# Adafruit_MicroUSB_Lipo.net
KiCad netlist of a schematic drawn in EAGLE
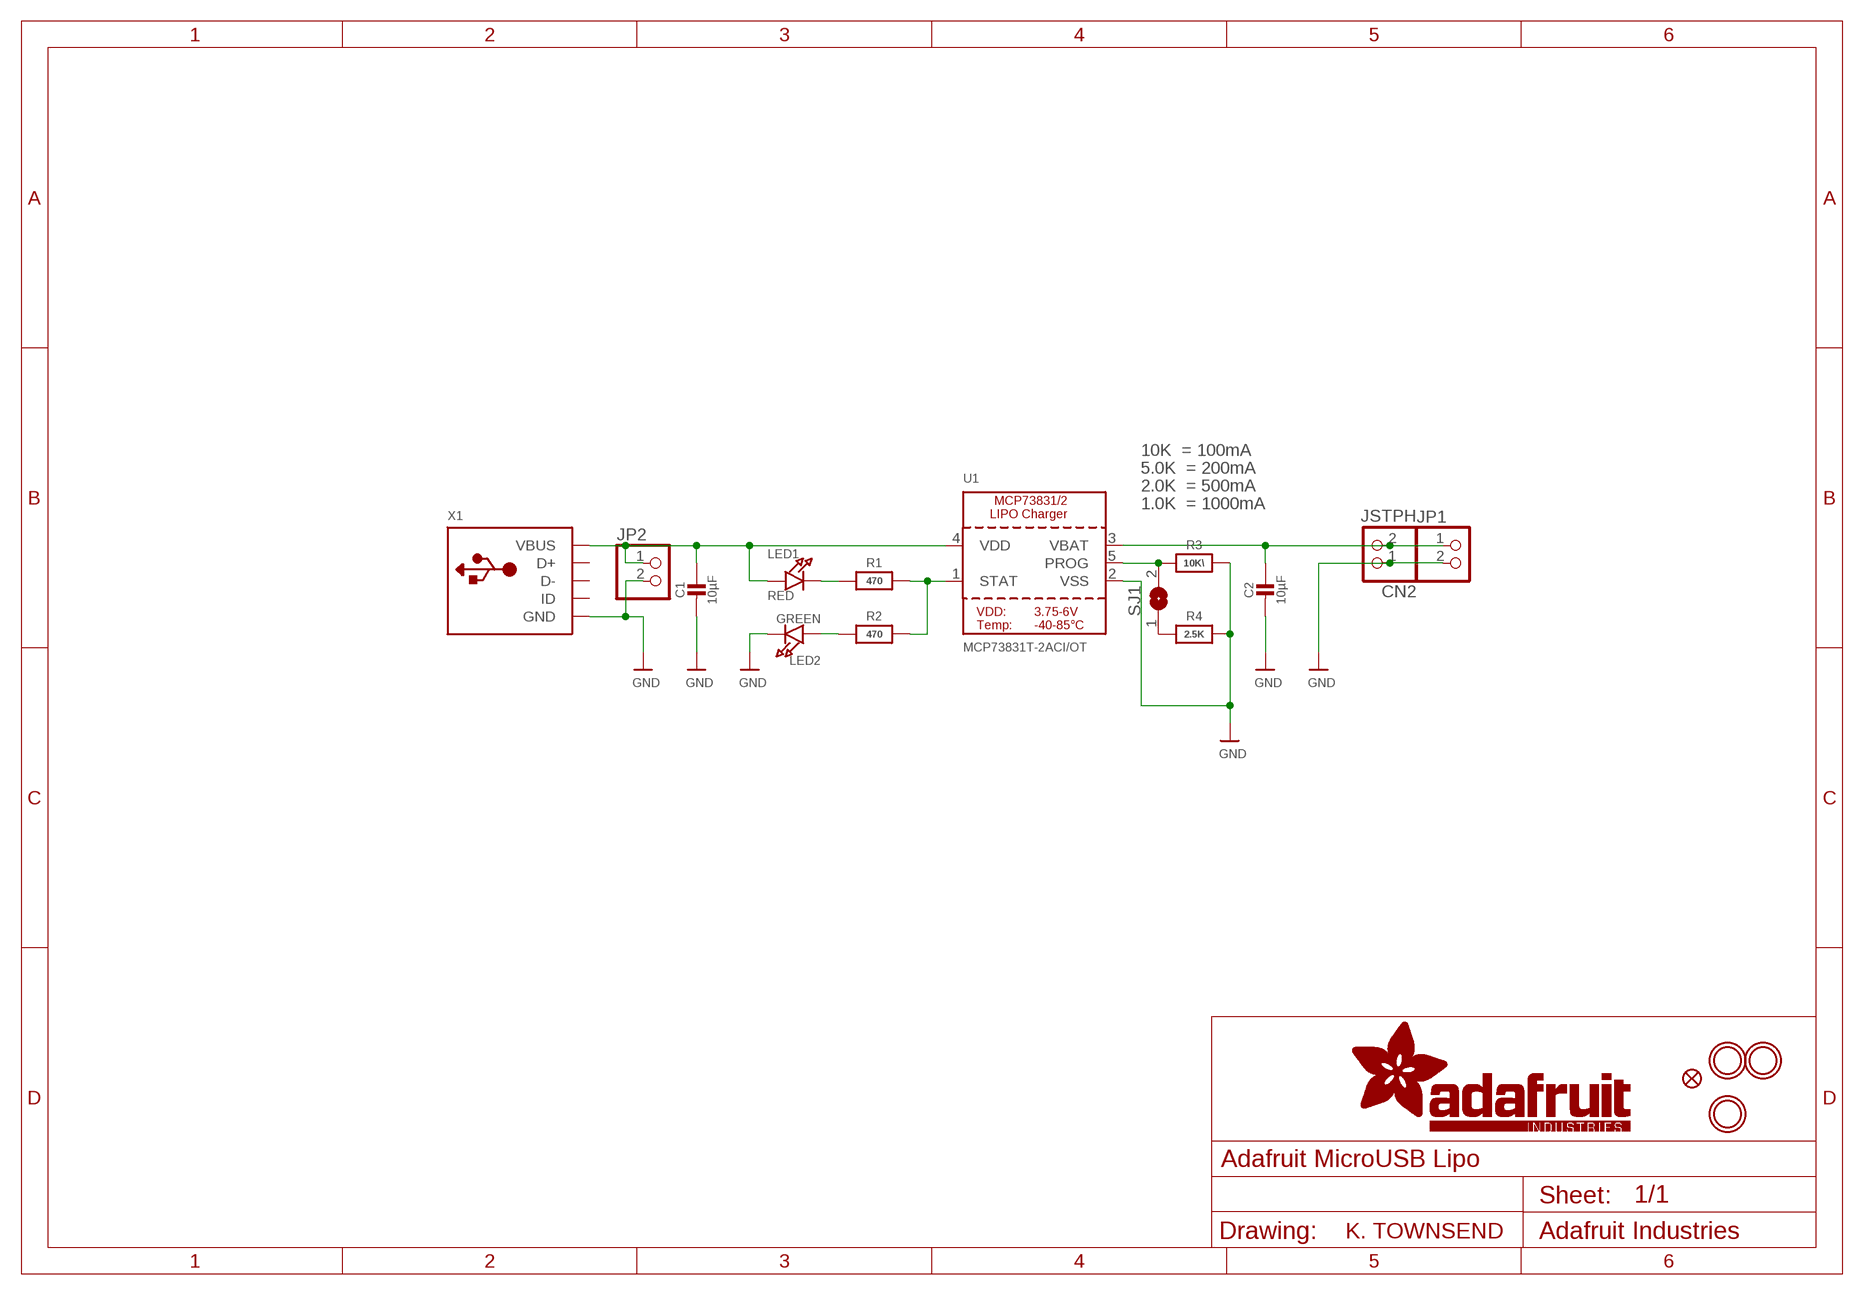
[diagram p0: schematic, sheet 1]

(export (version "E")
  (design (tool "Eeschema 10.0.6"))
  (components
    (comp (ref "C1")
      (value "10µF")
      (footprint "eagle-import:0805-NO")
      (libsource (lib "eagle-import") (part "CAP_CERAMIC0805-NOOUTLINE"))
    )
    (comp (ref "C2")
      (value "10µF")
      (footprint "eagle-import:0805-NO")
      (libsource (lib "eagle-import") (part "CAP_CERAMIC0805-NOOUTLINE"))
    )
    (comp (ref "CN2")
      (value "JSTPH")
      (footprint "eagle-import:JSTPH2")
      (libsource (lib "eagle-import") (part "JST_2PIN"))
    )
    (comp (ref "FID1")
      (value "FIDUCIAL\"\"")
      (footprint "eagle-import:FIDUCIAL_1MM")
      (libsource (lib "eagle-import") (part "FIDUCIAL{dblquote}{dblquote}"))
    )
    (comp (ref "JP1")
      (value "HEADER-1X2ROUND")
      (footprint "eagle-import:1X02_ROUND")
      (libsource (lib "eagle-import") (part "HEADER-1X2ROUND"))
    )
    (comp (ref "JP2")
      (value "HEADER-1X2ROUND")
      (footprint "eagle-import:1X02_ROUND")
      (libsource (lib "eagle-import") (part "HEADER-1X2ROUND"))
    )
    (comp (ref "LED1")
      (value "RED")
      (footprint "eagle-import:CHIPLED_0805_NOOUTLINE")
      (libsource (lib "eagle-import") (part "LED0805_NOOUTLINE"))
    )
    (comp (ref "LED2")
      (value "GREEN")
      (footprint "eagle-import:CHIPLED_0805_NOOUTLINE")
      (libsource (lib "eagle-import") (part "LED0805_NOOUTLINE"))
    )
    (comp (ref "R1")
      (value "470")
      (footprint "eagle-import:0805-NO")
      (libsource (lib "eagle-import") (part "RESISTOR0805_NOOUTLINE"))
    )
    (comp (ref "R2")
      (value "470")
      (footprint "eagle-import:0805-NO")
      (libsource (lib "eagle-import") (part "RESISTOR0805_NOOUTLINE"))
    )
    (comp (ref "R3")
      (value "10K\\")
      (footprint "eagle-import:0805-NO")
      (libsource (lib "eagle-import") (part "RESISTOR0805_NOOUTLINE"))
    )
    (comp (ref "R4")
      (value "2.5K")
      (footprint "eagle-import:0805-NO")
      (libsource (lib "eagle-import") (part "RESISTOR0805_NOOUTLINE"))
    )
    (comp (ref "SJ1")
      (value "SOLDERJUMPER")
      (footprint "eagle-import:SOLDERJUMPER_ARROW_NOPASTE")
      (libsource (lib "eagle-import") (part "SOLDERJUMPER"))
    )
    (comp (ref "U$9")
      (value "MOUNTINGHOLE2.5")
      (footprint "eagle-import:MOUNTINGHOLE_2.5_PLATED")
      (libsource (lib "eagle-import") (part "MOUNTINGHOLE2.5"))
    )
    (comp (ref "U$11")
      (value "MOUNTINGHOLE2.5")
      (footprint "eagle-import:MOUNTINGHOLE_2.5_PLATED")
      (libsource (lib "eagle-import") (part "MOUNTINGHOLE2.5"))
    )
    (comp (ref "U$12")
      (value "MOUNTINGHOLE2.5")
      (footprint "eagle-import:MOUNTINGHOLE_2.5_PLATED")
      (libsource (lib "eagle-import") (part "MOUNTINGHOLE2.5"))
    )
    (comp (ref "U1")
      (value "MCP73831T-2ACI/OT")
      (footprint "eagle-import:SOT23-5")
      (libsource (lib "eagle-import") (part "MCP73831/2"))
    )
    (comp (ref "X1")
      (value "USBMICRO_20329")
      (footprint "eagle-import:4UCONN_20329")
      (libsource (lib "eagle-import") (part "USBMICRO_20329"))
    )
  )
  (nets
    (net (code "1") (name "GND") (class "Default")
      (node (ref "C1") (pin "2") (pinfunction "2_2") (pintype "passive"))
      (node (ref "C2") (pin "2") (pinfunction "2_2") (pintype "passive"))
      (node (ref "CN2") (pin "1") (pinfunction "1_1") (pintype "passive"))
      (node (ref "JP1") (pin "2") (pinfunction "2_2") (pintype "passive"))
      (node (ref "JP2") (pin "2") (pinfunction "2_2") (pintype "passive"))
      (node (ref "LED2") (pin "C") (pinfunction "C_C") (pintype "passive"))
      (node (ref "R3") (pin "2") (pinfunction "2_2") (pintype "passive"))
      (node (ref "R4") (pin "2") (pinfunction "2_2") (pintype "passive"))
      (node (ref "U1") (pin "2") (pinfunction "VSS_2") (pintype "power_in"))
      (node (ref "X1") (pin "BASE@1") (pinfunction "GND_BASE@1") (pintype "power_in"))
      (node (ref "X1") (pin "BASE@2") (pinfunction "GND_BASE@2") (pintype "power_in"))
      (node (ref "X1") (pin "GND") (pinfunction "GND_GND") (pintype "power_in"))
      (node (ref "X1") (pin "SPRT@1") (pinfunction "GND_SPRT@1") (pintype "power_in"))
      (node (ref "X1") (pin "SPRT@2") (pinfunction "GND_SPRT@2") (pintype "power_in"))
      (node (ref "X1") (pin "SPRT@3") (pinfunction "GND_SPRT@3") (pintype "power_in"))
      (node (ref "X1") (pin "SPRT@4") (pinfunction "GND_SPRT@4") (pintype "power_in"))
    )
    (net (code "2") (name "Net-(LED1-PadC)") (class "Default")
      (node (ref "LED1") (pin "C") (pinfunction "C_C") (pintype "passive"))
      (node (ref "R1") (pin "1") (pinfunction "1_1") (pintype "passive"))
    )
    (net (code "3") (name "Net-(LED2-PadA)") (class "Default")
      (node (ref "LED2") (pin "A") (pinfunction "A_A") (pintype "passive"))
      (node (ref "R2") (pin "1") (pinfunction "1_1") (pintype "passive"))
    )
    (net (code "4") (name "Net-(R4-Pad1)") (class "Default")
      (node (ref "R4") (pin "1") (pinfunction "1_1") (pintype "passive"))
      (node (ref "SJ1") (pin "1") (pinfunction "1_1") (pintype "passive"))
    )
    (net (code "5") (name "Net-(U1-PROG)") (class "Default")
      (node (ref "R3") (pin "1") (pinfunction "1_1") (pintype "passive"))
      (node (ref "SJ1") (pin "2") (pinfunction "2_2") (pintype "passive"))
      (node (ref "U1") (pin "5") (pinfunction "PROG_5") (pintype "input"))
    )
    (net (code "6") (name "Net-(U1-STAT)") (class "Default")
      (node (ref "R1") (pin "2") (pinfunction "2_2") (pintype "passive"))
      (node (ref "R2") (pin "2") (pinfunction "2_2") (pintype "passive"))
      (node (ref "U1") (pin "1") (pinfunction "STAT_1") (pintype "output"))
    )
    (net (code "7") (name "Net-(U1-VBAT)") (class "Default")
      (node (ref "C2") (pin "1") (pinfunction "1_1") (pintype "passive"))
      (node (ref "CN2") (pin "2") (pinfunction "2_2") (pintype "passive"))
      (node (ref "JP1") (pin "1") (pinfunction "1_1") (pintype "passive"))
      (node (ref "U1") (pin "3") (pinfunction "VBAT_3") (pintype "power_in"))
    )
    (net (code "8") (name "Net-(U1-VDD)") (class "Default")
      (node (ref "C1") (pin "1") (pinfunction "1_1") (pintype "passive"))
      (node (ref "JP2") (pin "1") (pinfunction "1_1") (pintype "passive"))
      (node (ref "LED1") (pin "A") (pinfunction "A_A") (pintype "passive"))
      (node (ref "U1") (pin "4") (pinfunction "VDD_4") (pintype "power_in"))
      (node (ref "X1") (pin "VBUS") (pinfunction "VBUS_VBUS") (pintype "power_in"))
    )
    (net (code "9") (name "unconnected-(X1-PadD+)") (class "Default")
      (node (ref "X1") (pin "D+") (pinfunction "D+_D+") (pintype "bidirectional"))
    )
    (net (code "10") (name "unconnected-(X1-PadD-)") (class "Default")
      (node (ref "X1") (pin "D-") (pinfunction "D-_D-") (pintype "bidirectional"))
    )
    (net (code "11") (name "unconnected-(X1-PadID)") (class "Default")
      (node (ref "X1") (pin "ID") (pinfunction "ID_ID") (pintype "bidirectional"))
    )
  )
)
